# ETHIOLED.net
KiCad netlist of a schematic drawn in EAGLE
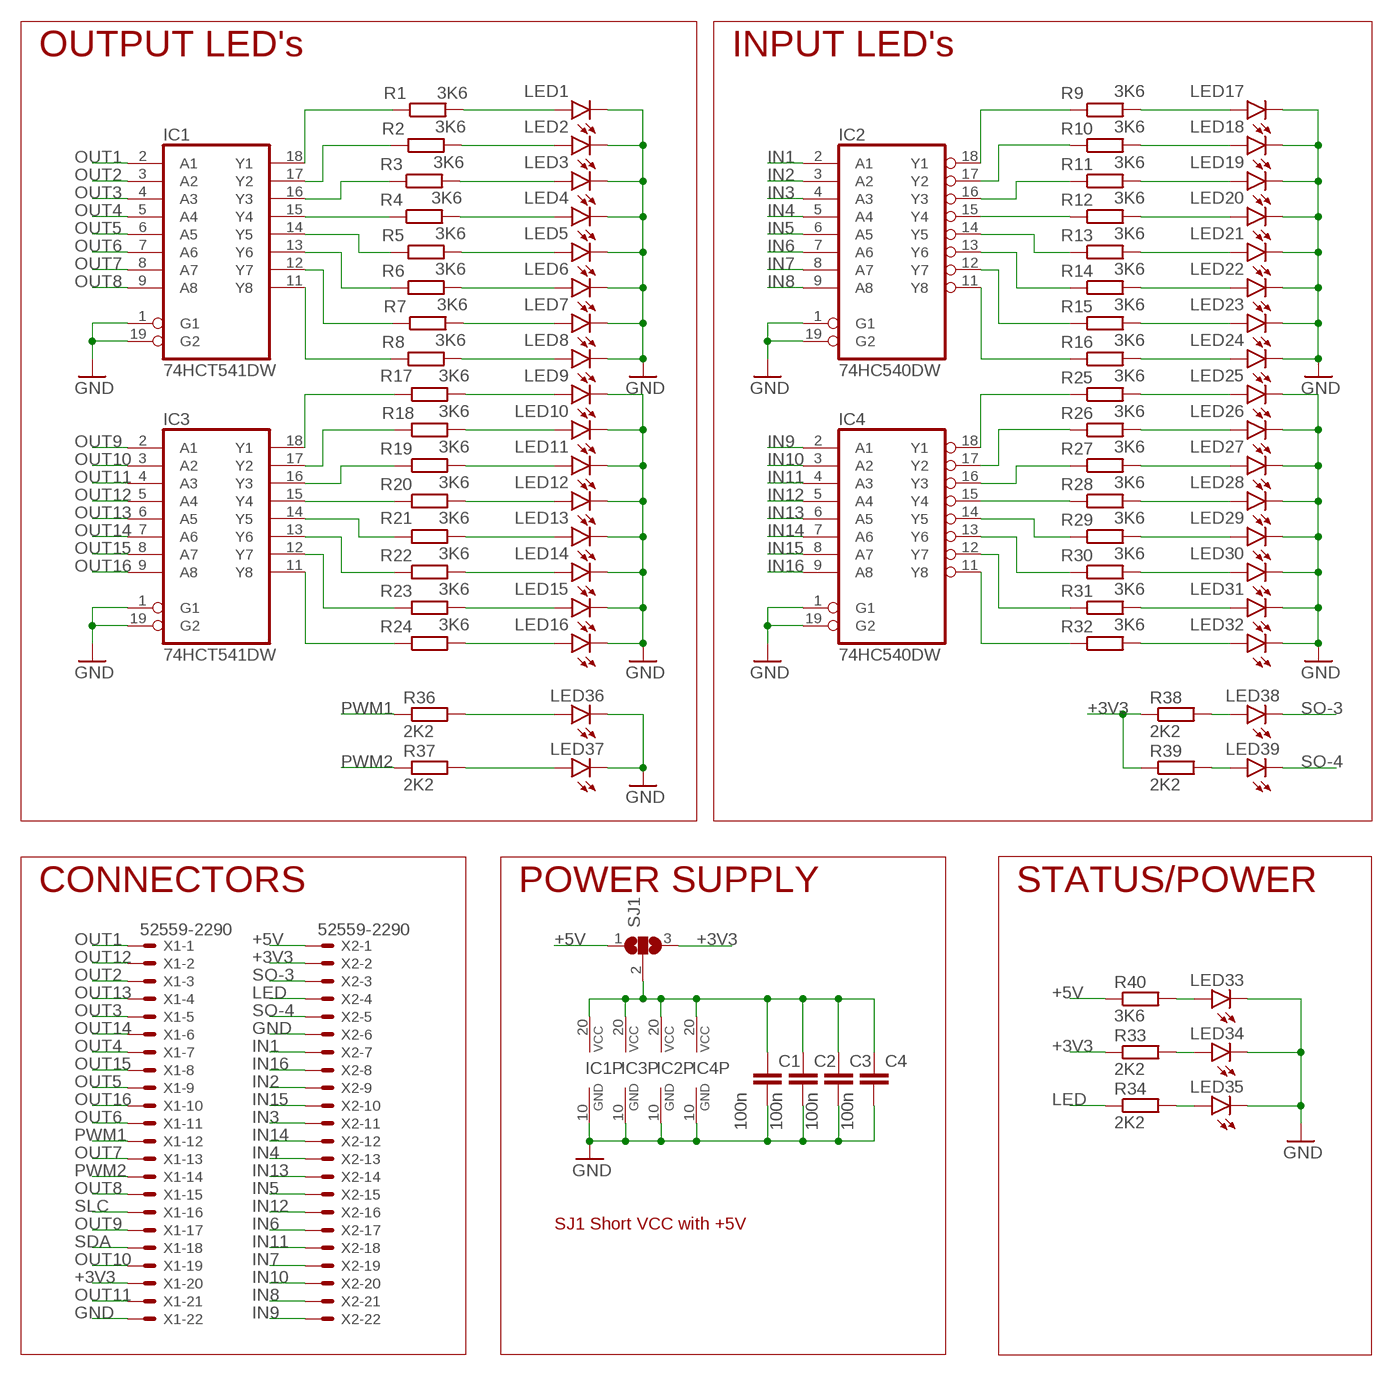
[diagram p0: schematic, sheet 1]

(export (version "E")
  (design (tool "Eeschema 10.0.6"))
  (components
    (comp (ref "C1")
      (value "100n")
      (footprint "eagle-import:C0805")
      (libsource (lib "eagle-import") (part "C-EUC0805"))
    )
    (comp (ref "C2")
      (value "100n")
      (footprint "eagle-import:C0805")
      (libsource (lib "eagle-import") (part "C-EUC0805"))
    )
    (comp (ref "C3")
      (value "100n")
      (footprint "eagle-import:C0805")
      (libsource (lib "eagle-import") (part "C-EUC0805"))
    )
    (comp (ref "C4")
      (value "100n")
      (footprint "eagle-import:C0805")
      (libsource (lib "eagle-import") (part "C-EUC0805"))
    )
    (comp (ref "IC1")
      (value "74HCT541DW")
      (footprint "eagle-import:SO20W")
      (libsource (lib "eagle-import") (part "74541DWHCT"))
    )
    (comp (ref "IC2")
      (value "74HC540DW")
      (footprint "eagle-import:SO20W")
      (libsource (lib "eagle-import") (part "74540DWHC"))
    )
    (comp (ref "IC3")
      (value "74HCT541DW")
      (footprint "eagle-import:SO20W")
      (libsource (lib "eagle-import") (part "74541DWHCT"))
    )
    (comp (ref "IC4")
      (value "74HC540DW")
      (footprint "eagle-import:SO20W")
      (libsource (lib "eagle-import") (part "74540DWHC"))
    )
    (comp (ref "LED1")
      (value "LEDSML1206")
      (footprint "eagle-import:SML1206")
      (libsource (lib "eagle-import") (part "LEDSML1206"))
    )
    (comp (ref "LED2")
      (value "LEDSML1206")
      (footprint "eagle-import:SML1206")
      (libsource (lib "eagle-import") (part "LEDSML1206"))
    )
    (comp (ref "LED3")
      (value "LEDSML1206")
      (footprint "eagle-import:SML1206")
      (libsource (lib "eagle-import") (part "LEDSML1206"))
    )
    (comp (ref "LED4")
      (value "LEDSML1206")
      (footprint "eagle-import:SML1206")
      (libsource (lib "eagle-import") (part "LEDSML1206"))
    )
    (comp (ref "LED5")
      (value "LEDSML1206")
      (footprint "eagle-import:SML1206")
      (libsource (lib "eagle-import") (part "LEDSML1206"))
    )
    (comp (ref "LED6")
      (value "LEDSML1206")
      (footprint "eagle-import:SML1206")
      (libsource (lib "eagle-import") (part "LEDSML1206"))
    )
    (comp (ref "LED7")
      (value "LEDSML1206")
      (footprint "eagle-import:SML1206")
      (libsource (lib "eagle-import") (part "LEDSML1206"))
    )
    (comp (ref "LED8")
      (value "LEDSML1206")
      (footprint "eagle-import:SML1206")
      (libsource (lib "eagle-import") (part "LEDSML1206"))
    )
    (comp (ref "LED9")
      (value "LEDSML1206")
      (footprint "eagle-import:SML1206")
      (libsource (lib "eagle-import") (part "LEDSML1206"))
    )
    (comp (ref "LED10")
      (value "LEDSML1206")
      (footprint "eagle-import:SML1206")
      (libsource (lib "eagle-import") (part "LEDSML1206"))
    )
    (comp (ref "LED11")
      (value "LEDSML1206")
      (footprint "eagle-import:SML1206")
      (libsource (lib "eagle-import") (part "LEDSML1206"))
    )
    (comp (ref "LED12")
      (value "LEDSML1206")
      (footprint "eagle-import:SML1206")
      (libsource (lib "eagle-import") (part "LEDSML1206"))
    )
    (comp (ref "LED13")
      (value "LEDSML1206")
      (footprint "eagle-import:SML1206")
      (libsource (lib "eagle-import") (part "LEDSML1206"))
    )
    (comp (ref "LED14")
      (value "LEDSML1206")
      (footprint "eagle-import:SML1206")
      (libsource (lib "eagle-import") (part "LEDSML1206"))
    )
    (comp (ref "LED15")
      (value "LEDSML1206")
      (footprint "eagle-import:SML1206")
      (libsource (lib "eagle-import") (part "LEDSML1206"))
    )
    (comp (ref "LED16")
      (value "LEDSML1206")
      (footprint "eagle-import:SML1206")
      (libsource (lib "eagle-import") (part "LEDSML1206"))
    )
    (comp (ref "LED17")
      (value "LEDSML1206")
      (footprint "eagle-import:SML1206")
      (libsource (lib "eagle-import") (part "LEDSML1206"))
    )
    (comp (ref "LED18")
      (value "LEDSML1206")
      (footprint "eagle-import:SML1206")
      (libsource (lib "eagle-import") (part "LEDSML1206"))
    )
    (comp (ref "LED19")
      (value "LEDSML1206")
      (footprint "eagle-import:SML1206")
      (libsource (lib "eagle-import") (part "LEDSML1206"))
    )
    (comp (ref "LED20")
      (value "LEDSML1206")
      (footprint "eagle-import:SML1206")
      (libsource (lib "eagle-import") (part "LEDSML1206"))
    )
    (comp (ref "LED21")
      (value "LEDSML1206")
      (footprint "eagle-import:SML1206")
      (libsource (lib "eagle-import") (part "LEDSML1206"))
    )
    (comp (ref "LED22")
      (value "LEDSML1206")
      (footprint "eagle-import:SML1206")
      (libsource (lib "eagle-import") (part "LEDSML1206"))
    )
    (comp (ref "LED23")
      (value "LEDSML1206")
      (footprint "eagle-import:SML1206")
      (libsource (lib "eagle-import") (part "LEDSML1206"))
    )
    (comp (ref "LED24")
      (value "LEDSML1206")
      (footprint "eagle-import:SML1206")
      (libsource (lib "eagle-import") (part "LEDSML1206"))
    )
    (comp (ref "LED25")
      (value "LEDSML1206")
      (footprint "eagle-import:SML1206")
      (libsource (lib "eagle-import") (part "LEDSML1206"))
    )
    (comp (ref "LED26")
      (value "LEDSML1206")
      (footprint "eagle-import:SML1206")
      (libsource (lib "eagle-import") (part "LEDSML1206"))
    )
    (comp (ref "LED27")
      (value "LEDSML1206")
      (footprint "eagle-import:SML1206")
      (libsource (lib "eagle-import") (part "LEDSML1206"))
    )
    (comp (ref "LED28")
      (value "LEDSML1206")
      (footprint "eagle-import:SML1206")
      (libsource (lib "eagle-import") (part "LEDSML1206"))
    )
    (comp (ref "LED29")
      (value "LEDSML1206")
      (footprint "eagle-import:SML1206")
      (libsource (lib "eagle-import") (part "LEDSML1206"))
    )
    (comp (ref "LED30")
      (value "LEDSML1206")
      (footprint "eagle-import:SML1206")
      (libsource (lib "eagle-import") (part "LEDSML1206"))
    )
    (comp (ref "LED31")
      (value "LEDSML1206")
      (footprint "eagle-import:SML1206")
      (libsource (lib "eagle-import") (part "LEDSML1206"))
    )
    (comp (ref "LED32")
      (value "LEDSML1206")
      (footprint "eagle-import:SML1206")
      (libsource (lib "eagle-import") (part "LEDSML1206"))
    )
    (comp (ref "LED33")
      (value "LEDSML1206")
      (footprint "eagle-import:SML1206")
      (libsource (lib "eagle-import") (part "LEDSML1206"))
    )
    (comp (ref "LED34")
      (value "LEDSML1206")
      (footprint "eagle-import:SML1206")
      (libsource (lib "eagle-import") (part "LEDSML1206"))
    )
    (comp (ref "LED35")
      (value "LEDSML1206")
      (footprint "eagle-import:SML1206")
      (libsource (lib "eagle-import") (part "LEDSML1206"))
    )
    (comp (ref "LED36")
      (value "LEDSML1206")
      (footprint "eagle-import:SML1206")
      (libsource (lib "eagle-import") (part "LEDSML1206"))
    )
    (comp (ref "LED37")
      (value "LEDSML1206")
      (footprint "eagle-import:SML1206")
      (libsource (lib "eagle-import") (part "LEDSML1206"))
    )
    (comp (ref "LED38")
      (value "LEDSML1206")
      (footprint "eagle-import:SML1206")
      (libsource (lib "eagle-import") (part "LEDSML1206"))
    )
    (comp (ref "LED39")
      (value "LEDSML1206")
      (footprint "eagle-import:SML1206")
      (libsource (lib "eagle-import") (part "LEDSML1206"))
    )
    (comp (ref "R1")
      (value "3K6")
      (footprint "eagle-import:R0805")
      (libsource (lib "eagle-import") (part "R-EU_R0805"))
    )
    (comp (ref "R2")
      (value "3K6")
      (footprint "eagle-import:R0805")
      (libsource (lib "eagle-import") (part "R-EU_R0805"))
    )
    (comp (ref "R3")
      (value "3K6")
      (footprint "eagle-import:R0805")
      (libsource (lib "eagle-import") (part "R-EU_R0805"))
    )
    (comp (ref "R4")
      (value "3K6")
      (footprint "eagle-import:R0805")
      (libsource (lib "eagle-import") (part "R-EU_R0805"))
    )
    (comp (ref "R5")
      (value "3K6")
      (footprint "eagle-import:R0805")
      (libsource (lib "eagle-import") (part "R-EU_R0805"))
    )
    (comp (ref "R6")
      (value "3K6")
      (footprint "eagle-import:R0805")
      (libsource (lib "eagle-import") (part "R-EU_R0805"))
    )
    (comp (ref "R7")
      (value "3K6")
      (footprint "eagle-import:R0805")
      (libsource (lib "eagle-import") (part "R-EU_R0805"))
    )
    (comp (ref "R8")
      (value "3K6")
      (footprint "eagle-import:R0805")
      (libsource (lib "eagle-import") (part "R-EU_R0805"))
    )
    (comp (ref "R9")
      (value "3K6")
      (footprint "eagle-import:R0805")
      (libsource (lib "eagle-import") (part "R-EU_R0805"))
    )
    (comp (ref "R10")
      (value "3K6")
      (footprint "eagle-import:R0805")
      (libsource (lib "eagle-import") (part "R-EU_R0805"))
    )
    (comp (ref "R11")
      (value "3K6")
      (footprint "eagle-import:R0805")
      (libsource (lib "eagle-import") (part "R-EU_R0805"))
    )
    (comp (ref "R12")
      (value "3K6")
      (footprint "eagle-import:R0805")
      (libsource (lib "eagle-import") (part "R-EU_R0805"))
    )
    (comp (ref "R13")
      (value "3K6")
      (footprint "eagle-import:R0805")
      (libsource (lib "eagle-import") (part "R-EU_R0805"))
    )
    (comp (ref "R14")
      (value "3K6")
      (footprint "eagle-import:R0805")
      (libsource (lib "eagle-import") (part "R-EU_R0805"))
    )
    (comp (ref "R15")
      (value "3K6")
      (footprint "eagle-import:R0805")
      (libsource (lib "eagle-import") (part "R-EU_R0805"))
    )
    (comp (ref "R16")
      (value "3K6")
      (footprint "eagle-import:R0805")
      (libsource (lib "eagle-import") (part "R-EU_R0805"))
    )
    (comp (ref "R17")
      (value "3K6")
      (footprint "eagle-import:R0805")
      (libsource (lib "eagle-import") (part "R-EU_R0805"))
    )
    (comp (ref "R18")
      (value "3K6")
      (footprint "eagle-import:R0805")
      (libsource (lib "eagle-import") (part "R-EU_R0805"))
    )
    (comp (ref "R19")
      (value "3K6")
      (footprint "eagle-import:R0805")
      (libsource (lib "eagle-import") (part "R-EU_R0805"))
    )
    (comp (ref "R20")
      (value "3K6")
      (footprint "eagle-import:R0805")
      (libsource (lib "eagle-import") (part "R-EU_R0805"))
    )
    (comp (ref "R21")
      (value "3K6")
      (footprint "eagle-import:R0805")
      (libsource (lib "eagle-import") (part "R-EU_R0805"))
    )
    (comp (ref "R22")
      (value "3K6")
      (footprint "eagle-import:R0805")
      (libsource (lib "eagle-import") (part "R-EU_R0805"))
    )
    (comp (ref "R23")
      (value "3K6")
      (footprint "eagle-import:R0805")
      (libsource (lib "eagle-import") (part "R-EU_R0805"))
    )
    (comp (ref "R24")
      (value "3K6")
      (footprint "eagle-import:R0805")
      (libsource (lib "eagle-import") (part "R-EU_R0805"))
    )
    (comp (ref "R25")
      (value "3K6")
      (footprint "eagle-import:R0805")
      (libsource (lib "eagle-import") (part "R-EU_R0805"))
    )
    (comp (ref "R26")
      (value "3K6")
      (footprint "eagle-import:R0805")
      (libsource (lib "eagle-import") (part "R-EU_R0805"))
    )
    (comp (ref "R27")
      (value "3K6")
      (footprint "eagle-import:R0805")
      (libsource (lib "eagle-import") (part "R-EU_R0805"))
    )
    (comp (ref "R28")
      (value "3K6")
      (footprint "eagle-import:R0805")
      (libsource (lib "eagle-import") (part "R-EU_R0805"))
    )
    (comp (ref "R29")
      (value "3K6")
      (footprint "eagle-import:R0805")
      (libsource (lib "eagle-import") (part "R-EU_R0805"))
    )
    (comp (ref "R30")
      (value "3K6")
      (footprint "eagle-import:R0805")
      (libsource (lib "eagle-import") (part "R-EU_R0805"))
    )
    (comp (ref "R31")
      (value "3K6")
      (footprint "eagle-import:R0805")
      (libsource (lib "eagle-import") (part "R-EU_R0805"))
    )
    (comp (ref "R32")
      (value "3K6")
      (footprint "eagle-import:R0805")
      (libsource (lib "eagle-import") (part "R-EU_R0805"))
    )
    (comp (ref "R33")
      (value "2K2")
      (footprint "eagle-import:R1206")
      (libsource (lib "eagle-import") (part "R-EU_R1206"))
    )
    (comp (ref "R34")
      (value "2K2")
      (footprint "eagle-import:R1206")
      (libsource (lib "eagle-import") (part "R-EU_R1206"))
    )
    (comp (ref "R36")
      (value "2K2")
      (footprint "eagle-import:R0805")
      (libsource (lib "eagle-import") (part "R-EU_R0805"))
    )
    (comp (ref "R37")
      (value "2K2")
      (footprint "eagle-import:R0805")
      (libsource (lib "eagle-import") (part "R-EU_R0805"))
    )
    (comp (ref "R38")
      (value "2K2")
      (footprint "eagle-import:R0805")
      (libsource (lib "eagle-import") (part "R-EU_R0805"))
    )
    (comp (ref "R39")
      (value "2K2")
      (footprint "eagle-import:R0805")
      (libsource (lib "eagle-import") (part "R-EU_R0805"))
    )
    (comp (ref "R40")
      (value "3K6")
      (footprint "eagle-import:R1206")
      (libsource (lib "eagle-import") (part "R-EU_R1206"))
    )
    (comp (ref "SJ1")
      (value "SJ2W")
      (footprint "eagle-import:SJ_2")
      (libsource (lib "eagle-import") (part "SJ2W"))
    )
    (comp (ref "X1")
      (value "52559-2290")
      (footprint "eagle-import:52559-2290")
      (fields (field (name "MF") "MOLEX"))
      (libsource (lib "eagle-import") (part "52559-2290"))
    )
    (comp (ref "X2")
      (value "52559-2290")
      (footprint "eagle-import:52559-2290")
      (fields (field (name "MF") "MOLEX"))
      (libsource (lib "eagle-import") (part "52559-2290"))
    )
  )
  (nets
    (net (code "1") (name "/+3V3") (class "Default")
      (node (ref "R33") (pin "1") (pinfunction "1_1") (pintype "passive"))
      (node (ref "R38") (pin "1") (pinfunction "1_1") (pintype "passive"))
      (node (ref "R39") (pin "1") (pinfunction "1_1") (pintype "passive"))
      (node (ref "SJ1") (pin "3") (pinfunction "3_3") (pintype "passive"))
      (node (ref "X1") (pin "20") (pinfunction "S_20") (pintype "passive"))
      (node (ref "X2") (pin "2") (pinfunction "S_2") (pintype "passive"))
    )
    (net (code "2") (name "/+5V") (class "Default")
      (node (ref "R40") (pin "1") (pinfunction "1_1") (pintype "passive"))
      (node (ref "SJ1") (pin "1") (pinfunction "1_1") (pintype "passive"))
      (node (ref "X2") (pin "1") (pinfunction "S_1") (pintype "passive"))
    )
    (net (code "3") (name "/IN1") (class "Default")
      (node (ref "IC2") (pin "2") (pinfunction "A1_2") (pintype "input"))
      (node (ref "X2") (pin "7") (pinfunction "S_7") (pintype "passive"))
    )
    (net (code "4") (name "/IN2") (class "Default")
      (node (ref "IC2") (pin "3") (pinfunction "A2_3") (pintype "input"))
      (node (ref "X2") (pin "9") (pinfunction "S_9") (pintype "passive"))
    )
    (net (code "5") (name "/IN3") (class "Default")
      (node (ref "IC2") (pin "4") (pinfunction "A3_4") (pintype "input"))
      (node (ref "X2") (pin "11") (pinfunction "S_11") (pintype "passive"))
    )
    (net (code "6") (name "/IN4") (class "Default")
      (node (ref "IC2") (pin "5") (pinfunction "A4_5") (pintype "input"))
      (node (ref "X2") (pin "13") (pinfunction "S_13") (pintype "passive"))
    )
    (net (code "7") (name "/IN5") (class "Default")
      (node (ref "IC2") (pin "6") (pinfunction "A5_6") (pintype "input"))
      (node (ref "X2") (pin "15") (pinfunction "S_15") (pintype "passive"))
    )
    (net (code "8") (name "/IN6") (class "Default")
      (node (ref "IC2") (pin "7") (pinfunction "A6_7") (pintype "input"))
      (node (ref "X2") (pin "17") (pinfunction "S_17") (pintype "passive"))
    )
    (net (code "9") (name "/IN7") (class "Default")
      (node (ref "IC2") (pin "8") (pinfunction "A7_8") (pintype "input"))
      (node (ref "X2") (pin "19") (pinfunction "S_19") (pintype "passive"))
    )
    (net (code "10") (name "/IN8") (class "Default")
      (node (ref "IC2") (pin "9") (pinfunction "A8_9") (pintype "input"))
      (node (ref "X2") (pin "21") (pinfunction "S_21") (pintype "passive"))
    )
    (net (code "11") (name "/IN9") (class "Default")
      (node (ref "IC4") (pin "2") (pinfunction "A1_2") (pintype "input"))
      (node (ref "X2") (pin "22") (pinfunction "S_22") (pintype "passive"))
    )
    (net (code "12") (name "/IN10") (class "Default")
      (node (ref "IC4") (pin "3") (pinfunction "A2_3") (pintype "input"))
      (node (ref "X2") (pin "20") (pinfunction "S_20") (pintype "passive"))
    )
    (net (code "13") (name "/IN11") (class "Default")
      (node (ref "IC4") (pin "4") (pinfunction "A3_4") (pintype "input"))
      (node (ref "X2") (pin "18") (pinfunction "S_18") (pintype "passive"))
    )
    (net (code "14") (name "/IN12") (class "Default")
      (node (ref "IC4") (pin "5") (pinfunction "A4_5") (pintype "input"))
      (node (ref "X2") (pin "16") (pinfunction "S_16") (pintype "passive"))
    )
    (net (code "15") (name "/IN13") (class "Default")
      (node (ref "IC4") (pin "6") (pinfunction "A5_6") (pintype "input"))
      (node (ref "X2") (pin "14") (pinfunction "S_14") (pintype "passive"))
    )
    (net (code "16") (name "/IN14") (class "Default")
      (node (ref "IC4") (pin "7") (pinfunction "A6_7") (pintype "input"))
      (node (ref "X2") (pin "12") (pinfunction "S_12") (pintype "passive"))
    )
    (net (code "17") (name "/IN15") (class "Default")
      (node (ref "IC4") (pin "8") (pinfunction "A7_8") (pintype "input"))
      (node (ref "X2") (pin "10") (pinfunction "S_10") (pintype "passive"))
    )
    (net (code "18") (name "/IN16") (class "Default")
      (node (ref "IC4") (pin "9") (pinfunction "A8_9") (pintype "input"))
      (node (ref "X2") (pin "8") (pinfunction "S_8") (pintype "passive"))
    )
    (net (code "19") (name "/LED") (class "Default")
      (node (ref "R34") (pin "1") (pinfunction "1_1") (pintype "passive"))
      (node (ref "X2") (pin "4") (pinfunction "S_4") (pintype "passive"))
    )
    (net (code "20") (name "/OUT1") (class "Default")
      (node (ref "IC1") (pin "2") (pinfunction "A1_2") (pintype "input"))
      (node (ref "X1") (pin "1") (pinfunction "S_1") (pintype "passive"))
    )
    (net (code "21") (name "/OUT2") (class "Default")
      (node (ref "IC1") (pin "3") (pinfunction "A2_3") (pintype "input"))
      (node (ref "X1") (pin "3") (pinfunction "S_3") (pintype "passive"))
    )
    (net (code "22") (name "/OUT3") (class "Default")
      (node (ref "IC1") (pin "4") (pinfunction "A3_4") (pintype "input"))
      (node (ref "X1") (pin "5") (pinfunction "S_5") (pintype "passive"))
    )
    (net (code "23") (name "/OUT4") (class "Default")
      (node (ref "IC1") (pin "5") (pinfunction "A4_5") (pintype "input"))
      (node (ref "X1") (pin "7") (pinfunction "S_7") (pintype "passive"))
    )
    (net (code "24") (name "/OUT5") (class "Default")
      (node (ref "IC1") (pin "6") (pinfunction "A5_6") (pintype "input"))
      (node (ref "X1") (pin "9") (pinfunction "S_9") (pintype "passive"))
    )
    (net (code "25") (name "/OUT6") (class "Default")
      (node (ref "IC1") (pin "7") (pinfunction "A6_7") (pintype "input"))
      (node (ref "X1") (pin "11") (pinfunction "S_11") (pintype "passive"))
    )
    (net (code "26") (name "/OUT7") (class "Default")
      (node (ref "IC1") (pin "8") (pinfunction "A7_8") (pintype "input"))
      (node (ref "X1") (pin "13") (pinfunction "S_13") (pintype "passive"))
    )
    (net (code "27") (name "/OUT8") (class "Default")
      (node (ref "IC1") (pin "9") (pinfunction "A8_9") (pintype "input"))
      (node (ref "X1") (pin "15") (pinfunction "S_15") (pintype "passive"))
    )
    (net (code "28") (name "/OUT9") (class "Default")
      (node (ref "IC3") (pin "2") (pinfunction "A1_2") (pintype "input"))
      (node (ref "X1") (pin "17") (pinfunction "S_17") (pintype "passive"))
    )
    (net (code "29") (name "/OUT10") (class "Default")
      (node (ref "IC3") (pin "3") (pinfunction "A2_3") (pintype "input"))
      (node (ref "X1") (pin "19") (pinfunction "S_19") (pintype "passive"))
    )
    (net (code "30") (name "/OUT11") (class "Default")
      (node (ref "IC3") (pin "4") (pinfunction "A3_4") (pintype "input"))
      (node (ref "X1") (pin "21") (pinfunction "S_21") (pintype "passive"))
    )
    (net (code "31") (name "/OUT12") (class "Default")
      (node (ref "IC3") (pin "5") (pinfunction "A4_5") (pintype "input"))
      (node (ref "X1") (pin "2") (pinfunction "S_2") (pintype "passive"))
    )
    (net (code "32") (name "/OUT13") (class "Default")
      (node (ref "IC3") (pin "6") (pinfunction "A5_6") (pintype "input"))
      (node (ref "X1") (pin "4") (pinfunction "S_4") (pintype "passive"))
    )
    (net (code "33") (name "/OUT14") (class "Default")
      (node (ref "IC3") (pin "7") (pinfunction "A6_7") (pintype "input"))
      (node (ref "X1") (pin "6") (pinfunction "S_6") (pintype "passive"))
    )
    (net (code "34") (name "/OUT15") (class "Default")
      (node (ref "IC3") (pin "8") (pinfunction "A7_8") (pintype "input"))
      (node (ref "X1") (pin "8") (pinfunction "S_8") (pintype "passive"))
    )
    (net (code "35") (name "/OUT16") (class "Default")
      (node (ref "IC3") (pin "9") (pinfunction "A8_9") (pintype "input"))
      (node (ref "X1") (pin "10") (pinfunction "S_10") (pintype "passive"))
    )
    (net (code "36") (name "/PWM1") (class "Default")
      (node (ref "R36") (pin "1") (pinfunction "1_1") (pintype "passive"))
      (node (ref "X1") (pin "12") (pinfunction "S_12") (pintype "passive"))
    )
    (net (code "37") (name "/PWM2") (class "Default")
      (node (ref "R37") (pin "1") (pinfunction "1_1") (pintype "passive"))
      (node (ref "X1") (pin "14") (pinfunction "S_14") (pintype "passive"))
    )
    (net (code "38") (name "/SDA") (class "Default")
      (node (ref "X1") (pin "18") (pinfunction "S_18") (pintype "passive"))
    )
    (net (code "39") (name "/SLC") (class "Default")
      (node (ref "X1") (pin "16") (pinfunction "S_16") (pintype "passive"))
    )
    (net (code "40") (name "/SO-3") (class "Default")
      (node (ref "LED38") (pin "C") (pinfunction "C_C") (pintype "passive"))
      (node (ref "X2") (pin "3") (pinfunction "S_3") (pintype "passive"))
    )
    (net (code "41") (name "/SO-4") (class "Default")
      (node (ref "LED39") (pin "C") (pinfunction "C_C") (pintype "passive"))
      (node (ref "X2") (pin "5") (pinfunction "S_5") (pintype "passive"))
    )
    (net (code "42") (name "GND") (class "Default")
      (node (ref "C1") (pin "2") (pinfunction "2_2") (pintype "passive"))
      (node (ref "C2") (pin "2") (pinfunction "2_2") (pintype "passive"))
      (node (ref "C3") (pin "2") (pinfunction "2_2") (pintype "passive"))
      (node (ref "C4") (pin "2") (pinfunction "2_2") (pintype "passive"))
      (node (ref "IC1") (pin "1") (pinfunction "G1_1") (pintype "input"))
      (node (ref "IC1") (pin "10") (pinfunction "GND_10") (pintype "power_in"))
      (node (ref "IC1") (pin "19") (pinfunction "G2_19") (pintype "input"))
      (node (ref "IC2") (pin "1") (pinfunction "G1_1") (pintype "input"))
      (node (ref "IC2") (pin "10") (pinfunction "GND_10") (pintype "power_in"))
      (node (ref "IC2") (pin "19") (pinfunction "G2_19") (pintype "input"))
      (node (ref "IC3") (pin "1") (pinfunction "G1_1") (pintype "input"))
      (node (ref "IC3") (pin "10") (pinfunction "GND_10") (pintype "power_in"))
      (node (ref "IC3") (pin "19") (pinfunction "G2_19") (pintype "input"))
      (node (ref "IC4") (pin "1") (pinfunction "G1_1") (pintype "input"))
      (node (ref "IC4") (pin "10") (pinfunction "GND_10") (pintype "power_in"))
      (node (ref "IC4") (pin "19") (pinfunction "G2_19") (pintype "input"))
      (node (ref "LED1") (pin "C") (pinfunction "C_C") (pintype "passive"))
      (node (ref "LED10") (pin "C") (pinfunction "C_C") (pintype "passive"))
      (node (ref "LED11") (pin "C") (pinfunction "C_C") (pintype "passive"))
      (node (ref "LED12") (pin "C") (pinfunction "C_C") (pintype "passive"))
      (node (ref "LED13") (pin "C") (pinfunction "C_C") (pintype "passive"))
      (node (ref "LED14") (pin "C") (pinfunction "C_C") (pintype "passive"))
      (node (ref "LED15") (pin "C") (pinfunction "C_C") (pintype "passive"))
      (node (ref "LED16") (pin "C") (pinfunction "C_C") (pintype "passive"))
      (node (ref "LED17") (pin "C") (pinfunction "C_C") (pintype "passive"))
      (node (ref "LED18") (pin "C") (pinfunction "C_C") (pintype "passive"))
      (node (ref "LED19") (pin "C") (pinfunction "C_C") (pintype "passive"))
      (node (ref "LED2") (pin "C") (pinfunction "C_C") (pintype "passive"))
      (node (ref "LED20") (pin "C") (pinfunction "C_C") (pintype "passive"))
      (node (ref "LED21") (pin "C") (pinfunction "C_C") (pintype "passive"))
      (node (ref "LED22") (pin "C") (pinfunction "C_C") (pintype "passive"))
      (node (ref "LED23") (pin "C") (pinfunction "C_C") (pintype "passive"))
      (node (ref "LED24") (pin "C") (pinfunction "C_C") (pintype "passive"))
      (node (ref "LED25") (pin "C") (pinfunction "C_C") (pintype "passive"))
      (node (ref "LED26") (pin "C") (pinfunction "C_C") (pintype "passive"))
      (node (ref "LED27") (pin "C") (pinfunction "C_C") (pintype "passive"))
      (node (ref "LED28") (pin "C") (pinfunction "C_C") (pintype "passive"))
      (node (ref "LED29") (pin "C") (pinfunction "C_C") (pintype "passive"))
      (node (ref "LED3") (pin "C") (pinfunction "C_C") (pintype "passive"))
      (node (ref "LED30") (pin "C") (pinfunction "C_C") (pintype "passive"))
      (node (ref "LED31") (pin "C") (pinfunction "C_C") (pintype "passive"))
      (node (ref "LED32") (pin "C") (pinfunction "C_C") (pintype "passive"))
      (node (ref "LED33") (pin "C") (pinfunction "C_C") (pintype "passive"))
      (node (ref "LED34") (pin "C") (pinfunction "C_C") (pintype "passive"))
      (node (ref "LED35") (pin "C") (pinfunction "C_C") (pintype "passive"))
      (node (ref "LED36") (pin "C") (pinfunction "C_C") (pintype "passive"))
      (node (ref "LED37") (pin "C") (pinfunction "C_C") (pintype "passive"))
      (node (ref "LED4") (pin "C") (pinfunction "C_C") (pintype "passive"))
      (node (ref "LED5") (pin "C") (pinfunction "C_C") (pintype "passive"))
      (node (ref "LED6") (pin "C") (pinfunction "C_C") (pintype "passive"))
      (node (ref "LED7") (pin "C") (pinfunction "C_C") (pintype "passive"))
      (node (ref "LED8") (pin "C") (pinfunction "C_C") (pintype "passive"))
      (node (ref "LED9") (pin "C") (pinfunction "C_C") (pintype "passive"))
      (node (ref "X1") (pin "22") (pinfunction "S_22") (pintype "passive"))
      (node (ref "X2") (pin "6") (pinfunction "S_6") (pintype "passive"))
    )
    (net (code "43") (name "Net-(IC1A-Y1)") (class "Default")
      (node (ref "IC1") (pin "18") (pinfunction "Y1_18") (pintype "tri_state"))
      (node (ref "R1") (pin "1") (pinfunction "1_1") (pintype "passive"))
    )
    (net (code "44") (name "Net-(IC1A-Y2)") (class "Default")
      (node (ref "IC1") (pin "17") (pinfunction "Y2_17") (pintype "tri_state"))
      (node (ref "R2") (pin "1") (pinfunction "1_1") (pintype "passive"))
    )
    (net (code "45") (name "Net-(IC1A-Y3)") (class "Default")
      (node (ref "IC1") (pin "16") (pinfunction "Y3_16") (pintype "tri_state"))
      (node (ref "R3") (pin "1") (pinfunction "1_1") (pintype "passive"))
    )
    (net (code "46") (name "Net-(IC1A-Y4)") (class "Default")
      (node (ref "IC1") (pin "15") (pinfunction "Y4_15") (pintype "tri_state"))
      (node (ref "R4") (pin "1") (pinfunction "1_1") (pintype "passive"))
    )
    (net (code "47") (name "Net-(IC1A-Y5)") (class "Default")
      (node (ref "IC1") (pin "14") (pinfunction "Y5_14") (pintype "tri_state"))
      (node (ref "R5") (pin "1") (pinfunction "1_1") (pintype "passive"))
    )
    (net (code "48") (name "Net-(IC1A-Y6)") (class "Default")
      (node (ref "IC1") (pin "13") (pinfunction "Y6_13") (pintype "tri_state"))
      (node (ref "R6") (pin "1") (pinfunction "1_1") (pintype "passive"))
    )
    (net (code "49") (name "Net-(IC1A-Y7)") (class "Default")
      (node (ref "IC1") (pin "12") (pinfunction "Y7_12") (pintype "tri_state"))
      (node (ref "R7") (pin "1") (pinfunction "1_1") (pintype "passive"))
    )
    (net (code "50") (name "Net-(IC1A-Y8)") (class "Default")
      (node (ref "IC1") (pin "11") (pinfunction "Y8_11") (pintype "tri_state"))
      (node (ref "R8") (pin "1") (pinfunction "1_1") (pintype "passive"))
    )
    (net (code "51") (name "Net-(IC1B-VCC)") (class "Default")
      (node (ref "C1") (pin "1") (pinfunction "1_1") (pintype "passive"))
      (node (ref "C2") (pin "1") (pinfunction "1_1") (pintype "passive"))
      (node (ref "C3") (pin "1") (pinfunction "1_1") (pintype "passive"))
      (node (ref "C4") (pin "1") (pinfunction "1_1") (pintype "passive"))
      (node (ref "IC1") (pin "20") (pinfunction "VCC_20") (pintype "power_in"))
      (node (ref "IC2") (pin "20") (pinfunction "VCC_20") (pintype "power_in"))
      (node (ref "IC3") (pin "20") (pinfunction "VCC_20") (pintype "power_in"))
      (node (ref "IC4") (pin "20") (pinfunction "VCC_20") (pintype "power_in"))
      (node (ref "SJ1") (pin "2") (pinfunction "2_2") (pintype "passive"))
    )
    (net (code "52") (name "Net-(IC2A-Y1)") (class "Default")
      (node (ref "IC2") (pin "18") (pinfunction "Y1_18") (pintype "tri_state"))
      (node (ref "R9") (pin "1") (pinfunction "1_1") (pintype "passive"))
    )
    (net (code "53") (name "Net-(IC2A-Y2)") (class "Default")
      (node (ref "IC2") (pin "17") (pinfunction "Y2_17") (pintype "tri_state"))
      (node (ref "R10") (pin "1") (pinfunction "1_1") (pintype "passive"))
    )
    (net (code "54") (name "Net-(IC2A-Y3)") (class "Default")
      (node (ref "IC2") (pin "16") (pinfunction "Y3_16") (pintype "tri_state"))
      (node (ref "R11") (pin "1") (pinfunction "1_1") (pintype "passive"))
    )
    (net (code "55") (name "Net-(IC2A-Y4)") (class "Default")
      (node (ref "IC2") (pin "15") (pinfunction "Y4_15") (pintype "tri_state"))
      (node (ref "R12") (pin "1") (pinfunction "1_1") (pintype "passive"))
    )
    (net (code "56") (name "Net-(IC2A-Y5)") (class "Default")
      (node (ref "IC2") (pin "14") (pinfunction "Y5_14") (pintype "tri_state"))
      (node (ref "R13") (pin "1") (pinfunction "1_1") (pintype "passive"))
    )
    (net (code "57") (name "Net-(IC2A-Y6)") (class "Default")
      (node (ref "IC2") (pin "13") (pinfunction "Y6_13") (pintype "tri_state"))
      (node (ref "R14") (pin "1") (pinfunction "1_1") (pintype "passive"))
    )
    (net (code "58") (name "Net-(IC2A-Y7)") (class "Default")
      (node (ref "IC2") (pin "12") (pinfunction "Y7_12") (pintype "tri_state"))
      (node (ref "R15") (pin "1") (pinfunction "1_1") (pintype "passive"))
    )
    (net (code "59") (name "Net-(IC2A-Y8)") (class "Default")
      (node (ref "IC2") (pin "11") (pinfunction "Y8_11") (pintype "tri_state"))
      (node (ref "R16") (pin "1") (pinfunction "1_1") (pintype "passive"))
    )
    (net (code "60") (name "Net-(IC3A-Y1)") (class "Default")
      (node (ref "IC3") (pin "18") (pinfunction "Y1_18") (pintype "tri_state"))
      (node (ref "R17") (pin "1") (pinfunction "1_1") (pintype "passive"))
    )
    (net (code "61") (name "Net-(IC3A-Y2)") (class "Default")
      (node (ref "IC3") (pin "17") (pinfunction "Y2_17") (pintype "tri_state"))
      (node (ref "R18") (pin "1") (pinfunction "1_1") (pintype "passive"))
    )
    (net (code "62") (name "Net-(IC3A-Y3)") (class "Default")
      (node (ref "IC3") (pin "16") (pinfunction "Y3_16") (pintype "tri_state"))
      (node (ref "R19") (pin "1") (pinfunction "1_1") (pintype "passive"))
    )
    (net (code "63") (name "Net-(IC3A-Y4)") (class "Default")
      (node (ref "IC3") (pin "15") (pinfunction "Y4_15") (pintype "tri_state"))
      (node (ref "R20") (pin "1") (pinfunction "1_1") (pintype "passive"))
    )
    (net (code "64") (name "Net-(IC3A-Y5)") (class "Default")
      (node (ref "IC3") (pin "14") (pinfunction "Y5_14") (pintype "tri_state"))
      (node (ref "R21") (pin "1") (pinfunction "1_1") (pintype "passive"))
    )
    (net (code "65") (name "Net-(IC3A-Y6)") (class "Default")
      (node (ref "IC3") (pin "13") (pinfunction "Y6_13") (pintype "tri_state"))
      (node (ref "R22") (pin "1") (pinfunction "1_1") (pintype "passive"))
    )
    (net (code "66") (name "Net-(IC3A-Y7)") (class "Default")
      (node (ref "IC3") (pin "12") (pinfunction "Y7_12") (pintype "tri_state"))
      (node (ref "R23") (pin "1") (pinfunction "1_1") (pintype "passive"))
    )
    (net (code "67") (name "Net-(IC3A-Y8)") (class "Default")
      (node (ref "IC3") (pin "11") (pinfunction "Y8_11") (pintype "tri_state"))
      (node (ref "R24") (pin "1") (pinfunction "1_1") (pintype "passive"))
    )
    (net (code "68") (name "Net-(IC4A-Y1)") (class "Default")
      (node (ref "IC4") (pin "18") (pinfunction "Y1_18") (pintype "tri_state"))
      (node (ref "R25") (pin "1") (pinfunction "1_1") (pintype "passive"))
    )
    (net (code "69") (name "Net-(IC4A-Y2)") (class "Default")
      (node (ref "IC4") (pin "17") (pinfunction "Y2_17") (pintype "tri_state"))
      (node (ref "R26") (pin "1") (pinfunction "1_1") (pintype "passive"))
    )
    (net (code "70") (name "Net-(IC4A-Y3)") (class "Default")
      (node (ref "IC4") (pin "16") (pinfunction "Y3_16") (pintype "tri_state"))
      (node (ref "R27") (pin "1") (pinfunction "1_1") (pintype "passive"))
    )
    (net (code "71") (name "Net-(IC4A-Y4)") (class "Default")
      (node (ref "IC4") (pin "15") (pinfunction "Y4_15") (pintype "tri_state"))
      (node (ref "R28") (pin "1") (pinfunction "1_1") (pintype "passive"))
    )
    (net (code "72") (name "Net-(IC4A-Y5)") (class "Default")
      (node (ref "IC4") (pin "14") (pinfunction "Y5_14") (pintype "tri_state"))
      (node (ref "R29") (pin "1") (pinfunction "1_1") (pintype "passive"))
    )
    (net (code "73") (name "Net-(IC4A-Y6)") (class "Default")
      (node (ref "IC4") (pin "13") (pinfunction "Y6_13") (pintype "tri_state"))
      (node (ref "R30") (pin "1") (pinfunction "1_1") (pintype "passive"))
    )
    (net (code "74") (name "Net-(IC4A-Y7)") (class "Default")
      (node (ref "IC4") (pin "12") (pinfunction "Y7_12") (pintype "tri_state"))
      (node (ref "R31") (pin "1") (pinfunction "1_1") (pintype "passive"))
    )
    (net (code "75") (name "Net-(IC4A-Y8)") (class "Default")
      (node (ref "IC4") (pin "11") (pinfunction "Y8_11") (pintype "tri_state"))
      (node (ref "R32") (pin "1") (pinfunction "1_1") (pintype "passive"))
    )
    (net (code "76") (name "Net-(LED1-PadA)") (class "Default")
      (node (ref "LED1") (pin "A") (pinfunction "A_A") (pintype "passive"))
      (node (ref "R1") (pin "2") (pinfunction "2_2") (pintype "passive"))
    )
    (net (code "77") (name "Net-(LED2-PadA)") (class "Default")
      (node (ref "LED2") (pin "A") (pinfunction "A_A") (pintype "passive"))
      (node (ref "R2") (pin "2") (pinfunction "2_2") (pintype "passive"))
    )
    (net (code "78") (name "Net-(LED3-PadA)") (class "Default")
      (node (ref "LED3") (pin "A") (pinfunction "A_A") (pintype "passive"))
      (node (ref "R3") (pin "2") (pinfunction "2_2") (pintype "passive"))
    )
    (net (code "79") (name "Net-(LED4-PadA)") (class "Default")
      (node (ref "LED4") (pin "A") (pinfunction "A_A") (pintype "passive"))
      (node (ref "R4") (pin "2") (pinfunction "2_2") (pintype "passive"))
    )
    (net (code "80") (name "Net-(LED5-PadA)") (class "Default")
      (node (ref "LED5") (pin "A") (pinfunction "A_A") (pintype "passive"))
      (node (ref "R5") (pin "2") (pinfunction "2_2") (pintype "passive"))
    )
    (net (code "81") (name "Net-(LED6-PadA)") (class "Default")
      (node (ref "LED6") (pin "A") (pinfunction "A_A") (pintype "passive"))
      (node (ref "R6") (pin "2") (pinfunction "2_2") (pintype "passive"))
    )
    (net (code "82") (name "Net-(LED7-PadA)") (class "Default")
      (node (ref "LED7") (pin "A") (pinfunction "A_A") (pintype "passive"))
      (node (ref "R7") (pin "2") (pinfunction "2_2") (pintype "passive"))
    )
    (net (code "83") (name "Net-(LED8-PadA)") (class "Default")
      (node (ref "LED8") (pin "A") (pinfunction "A_A") (pintype "passive"))
      (node (ref "R8") (pin "2") (pinfunction "2_2") (pintype "passive"))
    )
    (net (code "84") (name "Net-(LED9-PadA)") (class "Default")
      (node (ref "LED9") (pin "A") (pinfunction "A_A") (pintype "passive"))
      (node (ref "R17") (pin "2") (pinfunction "2_2") (pintype "passive"))
    )
    (net (code "85") (name "Net-(LED10-PadA)") (class "Default")
      (node (ref "LED10") (pin "A") (pinfunction "A_A") (pintype "passive"))
      (node (ref "R18") (pin "2") (pinfunction "2_2") (pintype "passive"))
    )
    (net (code "86") (name "Net-(LED11-PadA)") (class "Default")
      (node (ref "LED11") (pin "A") (pinfunction "A_A") (pintype "passive"))
      (node (ref "R19") (pin "2") (pinfunction "2_2") (pintype "passive"))
    )
    (net (code "87") (name "Net-(LED12-PadA)") (class "Default")
      (node (ref "LED12") (pin "A") (pinfunction "A_A") (pintype "passive"))
      (node (ref "R20") (pin "2") (pinfunction "2_2") (pintype "passive"))
    )
    (net (code "88") (name "Net-(LED13-PadA)") (class "Default")
      (node (ref "LED13") (pin "A") (pinfunction "A_A") (pintype "passive"))
      (node (ref "R21") (pin "2") (pinfunction "2_2") (pintype "passive"))
    )
    (net (code "89") (name "Net-(LED14-PadA)") (class "Default")
      (node (ref "LED14") (pin "A") (pinfunction "A_A") (pintype "passive"))
      (node (ref "R22") (pin "2") (pinfunction "2_2") (pintype "passive"))
    )
    (net (code "90") (name "Net-(LED15-PadA)") (class "Default")
      (node (ref "LED15") (pin "A") (pinfunction "A_A") (pintype "passive"))
      (node (ref "R23") (pin "2") (pinfunction "2_2") (pintype "passive"))
    )
    (net (code "91") (name "Net-(LED16-PadA)") (class "Default")
      (node (ref "LED16") (pin "A") (pinfunction "A_A") (pintype "passive"))
      (node (ref "R24") (pin "2") (pinfunction "2_2") (pintype "passive"))
    )
    (net (code "92") (name "Net-(LED17-PadA)") (class "Default")
      (node (ref "LED17") (pin "A") (pinfunction "A_A") (pintype "passive"))
      (node (ref "R9") (pin "2") (pinfunction "2_2") (pintype "passive"))
    )
    (net (code "93") (name "Net-(LED18-PadA)") (class "Default")
      (node (ref "LED18") (pin "A") (pinfunction "A_A") (pintype "passive"))
      (node (ref "R10") (pin "2") (pinfunction "2_2") (pintype "passive"))
    )
    (net (code "94") (name "Net-(LED19-PadA)") (class "Default")
      (node (ref "LED19") (pin "A") (pinfunction "A_A") (pintype "passive"))
      (node (ref "R11") (pin "2") (pinfunction "2_2") (pintype "passive"))
    )
    (net (code "95") (name "Net-(LED20-PadA)") (class "Default")
      (node (ref "LED20") (pin "A") (pinfunction "A_A") (pintype "passive"))
      (node (ref "R12") (pin "2") (pinfunction "2_2") (pintype "passive"))
    )
    (net (code "96") (name "Net-(LED21-PadA)") (class "Default")
      (node (ref "LED21") (pin "A") (pinfunction "A_A") (pintype "passive"))
      (node (ref "R13") (pin "2") (pinfunction "2_2") (pintype "passive"))
    )
    (net (code "97") (name "Net-(LED22-PadA)") (class "Default")
      (node (ref "LED22") (pin "A") (pinfunction "A_A") (pintype "passive"))
      (node (ref "R14") (pin "2") (pinfunction "2_2") (pintype "passive"))
    )
    (net (code "98") (name "Net-(LED23-PadA)") (class "Default")
      (node (ref "LED23") (pin "A") (pinfunction "A_A") (pintype "passive"))
      (node (ref "R15") (pin "2") (pinfunction "2_2") (pintype "passive"))
    )
    (net (code "99") (name "Net-(LED24-PadA)") (class "Default")
      (node (ref "LED24") (pin "A") (pinfunction "A_A") (pintype "passive"))
      (node (ref "R16") (pin "2") (pinfunction "2_2") (pintype "passive"))
    )
    (net (code "100") (name "Net-(LED25-PadA)") (class "Default")
      (node (ref "LED25") (pin "A") (pinfunction "A_A") (pintype "passive"))
      (node (ref "R25") (pin "2") (pinfunction "2_2") (pintype "passive"))
    )
    (net (code "101") (name "Net-(LED26-PadA)") (class "Default")
      (node (ref "LED26") (pin "A") (pinfunction "A_A") (pintype "passive"))
      (node (ref "R26") (pin "2") (pinfunction "2_2") (pintype "passive"))
    )
    (net (code "102") (name "Net-(LED27-PadA)") (class "Default")
      (node (ref "LED27") (pin "A") (pinfunction "A_A") (pintype "passive"))
      (node (ref "R27") (pin "2") (pinfunction "2_2") (pintype "passive"))
    )
    (net (code "103") (name "Net-(LED28-PadA)") (class "Default")
      (node (ref "LED28") (pin "A") (pinfunction "A_A") (pintype "passive"))
      (node (ref "R28") (pin "2") (pinfunction "2_2") (pintype "passive"))
    )
    (net (code "104") (name "Net-(LED29-PadA)") (class "Default")
      (node (ref "LED29") (pin "A") (pinfunction "A_A") (pintype "passive"))
      (node (ref "R29") (pin "2") (pinfunction "2_2") (pintype "passive"))
    )
    (net (code "105") (name "Net-(LED30-PadA)") (class "Default")
      (node (ref "LED30") (pin "A") (pinfunction "A_A") (pintype "passive"))
      (node (ref "R30") (pin "2") (pinfunction "2_2") (pintype "passive"))
    )
    (net (code "106") (name "Net-(LED31-PadA)") (class "Default")
      (node (ref "LED31") (pin "A") (pinfunction "A_A") (pintype "passive"))
      (node (ref "R31") (pin "2") (pinfunction "2_2") (pintype "passive"))
    )
    (net (code "107") (name "Net-(LED32-PadA)") (class "Default")
      (node (ref "LED32") (pin "A") (pinfunction "A_A") (pintype "passive"))
      (node (ref "R32") (pin "2") (pinfunction "2_2") (pintype "passive"))
    )
    (net (code "108") (name "Net-(LED33-PadA)") (class "Default")
      (node (ref "LED33") (pin "A") (pinfunction "A_A") (pintype "passive"))
      (node (ref "R40") (pin "2") (pinfunction "2_2") (pintype "passive"))
    )
    (net (code "109") (name "Net-(LED34-PadA)") (class "Default")
      (node (ref "LED34") (pin "A") (pinfunction "A_A") (pintype "passive"))
      (node (ref "R33") (pin "2") (pinfunction "2_2") (pintype "passive"))
    )
    (net (code "110") (name "Net-(LED35-PadA)") (class "Default")
      (node (ref "LED35") (pin "A") (pinfunction "A_A") (pintype "passive"))
      (node (ref "R34") (pin "2") (pinfunction "2_2") (pintype "passive"))
    )
    (net (code "111") (name "Net-(LED36-PadA)") (class "Default")
      (node (ref "LED36") (pin "A") (pinfunction "A_A") (pintype "passive"))
      (node (ref "R36") (pin "2") (pinfunction "2_2") (pintype "passive"))
    )
    (net (code "112") (name "Net-(LED37-PadA)") (class "Default")
      (node (ref "LED37") (pin "A") (pinfunction "A_A") (pintype "passive"))
      (node (ref "R37") (pin "2") (pinfunction "2_2") (pintype "passive"))
    )
    (net (code "113") (name "Net-(LED38-PadA)") (class "Default")
      (node (ref "LED38") (pin "A") (pinfunction "A_A") (pintype "passive"))
      (node (ref "R38") (pin "2") (pinfunction "2_2") (pintype "passive"))
    )
    (net (code "114") (name "Net-(LED39-PadA)") (class "Default")
      (node (ref "LED39") (pin "A") (pinfunction "A_A") (pintype "passive"))
      (node (ref "R39") (pin "2") (pinfunction "2_2") (pintype "passive"))
    )
  )
)
